# switch_7btn.net
KiCad netlist of a schematic drawn in EAGLE
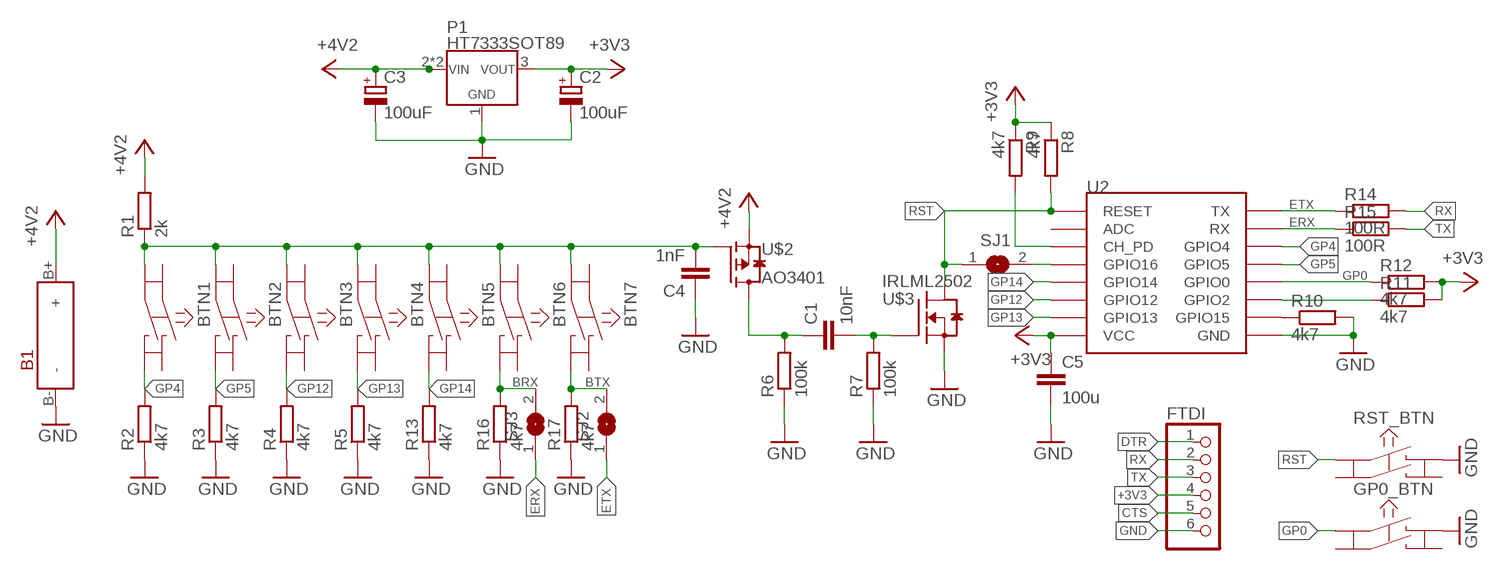
[diagram p0: schematic, sheet 1]

(export (version "E")
  (design (tool "Eeschema 10.0.6"))
  (components
    (comp (ref "B1")
      (value "18650_1X")
      (footprint "eagle-import:18650_HOLDER_1X")
      (libsource (lib "eagle-import") (part "18650_1X"))
    )
    (comp (ref "BTN1")
      (value "KSM611A")
      (footprint "eagle-import:KSM611A")
      (libsource (lib "eagle-import") (part "KSM611A"))
    )
    (comp (ref "BTN2")
      (value "KSM611A")
      (footprint "eagle-import:KSM611A")
      (libsource (lib "eagle-import") (part "KSM611A"))
    )
    (comp (ref "BTN3")
      (value "KSM611A")
      (footprint "eagle-import:KSM611A")
      (libsource (lib "eagle-import") (part "KSM611A"))
    )
    (comp (ref "BTN4")
      (value "KSM611A")
      (footprint "eagle-import:KSM611A")
      (libsource (lib "eagle-import") (part "KSM611A"))
    )
    (comp (ref "BTN5")
      (value "KSM611A")
      (footprint "eagle-import:KSM611A")
      (libsource (lib "eagle-import") (part "KSM611A"))
    )
    (comp (ref "BTN6")
      (value "KSM611A")
      (footprint "eagle-import:KSM611A")
      (libsource (lib "eagle-import") (part "KSM611A"))
    )
    (comp (ref "BTN7")
      (value "KSM611A")
      (footprint "eagle-import:KSM611A")
      (libsource (lib "eagle-import") (part "KSM611A"))
    )
    (comp (ref "C1")
      (value "10nF")
      (footprint "eagle-import:C025-025X050")
      (libsource (lib "eagle-import") (part "C-EU025-025X050"))
    )
    (comp (ref "C2")
      (value "100uF")
      (footprint "eagle-import:E5-8,5")
      (libsource (lib "eagle-import") (part "CPOL-EUE5-8.5"))
    )
    (comp (ref "C3")
      (value "100uF")
      (footprint "eagle-import:E5-8,5")
      (libsource (lib "eagle-import") (part "CPOL-EUE5-8.5"))
    )
    (comp (ref "C4")
      (value "1nF")
      (footprint "eagle-import:C025-025X050")
      (libsource (lib "eagle-import") (part "C-EU025-025X050"))
    )
    (comp (ref "C5")
      (value "100u")
      (footprint "eagle-import:C1206")
      (libsource (lib "eagle-import") (part "C-EUC1206"))
    )
    (comp (ref "FTDI")
      (value "PINHD-1X06_2.54-S")
      (footprint "eagle-import:1X06-S")
      (libsource (lib "eagle-import") (part "PINHD-1X06_2.54-S"))
    )
    (comp (ref "GP0_BTN")
      (value "KSM611A")
      (footprint "eagle-import:KSM611A")
      (libsource (lib "eagle-import") (part "KSM611A"))
    )
    (comp (ref "P1")
      (value "HT7333SOT89")
      (footprint "eagle-import:SOT89")
      (libsource (lib "eagle-import") (part "HT7333SOT89"))
    )
    (comp (ref "R1")
      (value "2k")
      (footprint "eagle-import:MULTI_RESISTOR")
      (libsource (lib "eagle-import") (part "R-EU_MULTI"))
    )
    (comp (ref "R2")
      (value "4k7")
      (footprint "eagle-import:MULTI_RESISTOR")
      (libsource (lib "eagle-import") (part "R-EU_MULTI"))
    )
    (comp (ref "R3")
      (value "4k7")
      (footprint "eagle-import:MULTI_RESISTOR")
      (libsource (lib "eagle-import") (part "R-EU_MULTI"))
    )
    (comp (ref "R4")
      (value "4k7")
      (footprint "eagle-import:MULTI_RESISTOR")
      (libsource (lib "eagle-import") (part "R-EU_MULTI"))
    )
    (comp (ref "R5")
      (value "4k7")
      (footprint "eagle-import:MULTI_RESISTOR")
      (libsource (lib "eagle-import") (part "R-EU_MULTI"))
    )
    (comp (ref "R6")
      (value "100k")
      (footprint "eagle-import:MULTI_RESISTOR")
      (libsource (lib "eagle-import") (part "R-EU_MULTI"))
    )
    (comp (ref "R7")
      (value "100k")
      (footprint "eagle-import:MULTI_RESISTOR")
      (libsource (lib "eagle-import") (part "R-EU_MULTI"))
    )
    (comp (ref "R8")
      (value "4k7")
      (footprint "eagle-import:MULTI_RESISTOR")
      (libsource (lib "eagle-import") (part "R-EU_MULTI"))
    )
    (comp (ref "R9")
      (value "4k7")
      (footprint "eagle-import:MULTI_RESISTOR")
      (libsource (lib "eagle-import") (part "R-EU_MULTI"))
    )
    (comp (ref "R10")
      (value "4k7")
      (footprint "eagle-import:MULTI_RESISTOR")
      (libsource (lib "eagle-import") (part "R-EU_MULTI"))
    )
    (comp (ref "R11")
      (value "4k7")
      (footprint "eagle-import:MULTI_RESISTOR")
      (libsource (lib "eagle-import") (part "R-EU_MULTI"))
    )
    (comp (ref "R12")
      (value "4k7")
      (footprint "eagle-import:MULTI_RESISTOR")
      (libsource (lib "eagle-import") (part "R-EU_MULTI"))
    )
    (comp (ref "R13")
      (value "4k7")
      (footprint "eagle-import:MULTI_RESISTOR")
      (libsource (lib "eagle-import") (part "R-EU_MULTI"))
    )
    (comp (ref "R14")
      (value "100R")
      (footprint "eagle-import:MULTI_RESISTOR")
      (libsource (lib "eagle-import") (part "R-EU_MULTI"))
    )
    (comp (ref "R15")
      (value "100R")
      (footprint "eagle-import:MULTI_RESISTOR")
      (libsource (lib "eagle-import") (part "R-EU_MULTI"))
    )
    (comp (ref "R16")
      (value "4k7")
      (footprint "eagle-import:MULTI_RESISTOR")
      (libsource (lib "eagle-import") (part "R-EU_MULTI"))
    )
    (comp (ref "R17")
      (value "4k7")
      (footprint "eagle-import:MULTI_RESISTOR")
      (libsource (lib "eagle-import") (part "R-EU_MULTI"))
    )
    (comp (ref "RST_BTN")
      (value "KSM611A")
      (footprint "eagle-import:KSM611A")
      (libsource (lib "eagle-import") (part "KSM611A"))
    )
    (comp (ref "SJ1") (value "SJ") (footprint "eagle-import:SJ") (libsource (lib "eagle-import") (part "SJ")))
    (comp (ref "SJ2") (value "SJ") (footprint "eagle-import:SJ") (libsource (lib "eagle-import") (part "SJ")))
    (comp (ref "SJ3") (value "SJ") (footprint "eagle-import:SJ") (libsource (lib "eagle-import") (part "SJ")))
    (comp (ref "U$2")
      (value "AO3401")
      (footprint "eagle-import:SOT23")
      (libsource (lib "eagle-import") (part "P-CH_AO3401"))
    )
    (comp (ref "U$3")
      (value "IRLML2502")
      (footprint "eagle-import:SOT23")
      (libsource (lib "eagle-import") (part "N-CH_IRLML2502"))
    )
    (comp (ref "U2")
      (value "ESP12SMD")
      (footprint "eagle-import:ESP12-SMD")
      (libsource (lib "eagle-import") (part "ESP12SMD"))
    )
  )
  (nets
    (net (code "1") (name "+3V3") (class "Default")
      (node (ref "C2") (pin "+") (pinfunction "+_+") (pintype "passive"))
      (node (ref "C5") (pin "1") (pinfunction "1_1") (pintype "passive"))
      (node (ref "FTDI") (pin "4") (pinfunction "4_4") (pintype "passive"))
      (node (ref "P1") (pin "3") (pinfunction "VOUT_3") (pintype "power_in"))
      (node (ref "R11") (pin "2@1") (pinfunction "2_2@1") (pintype "passive"))
      (node (ref "R11") (pin "2@2") (pinfunction "2_2@2") (pintype "passive"))
      (node (ref "R12") (pin "2@1") (pinfunction "2_2@1") (pintype "passive"))
      (node (ref "R12") (pin "2@2") (pinfunction "2_2@2") (pintype "passive"))
      (node (ref "R8") (pin "1@1") (pinfunction "1_1@1") (pintype "passive"))
      (node (ref "R8") (pin "1@2") (pinfunction "1_1@2") (pintype "passive"))
      (node (ref "R9") (pin "1@1") (pinfunction "1_1@1") (pintype "passive"))
      (node (ref "R9") (pin "1@2") (pinfunction "1_1@2") (pintype "passive"))
      (node (ref "U2") (pin "VCC") (pinfunction "VCC_VCC") (pintype "bidirectional"))
    )
    (net (code "2") (name "+4V2") (class "Default")
      (node (ref "B1") (pin "B+") (pinfunction "+_B+") (pintype "power_in"))
      (node (ref "C3") (pin "+") (pinfunction "+_+") (pintype "passive"))
      (node (ref "P1") (pin "2") (pinfunction "VIN_2") (pintype "power_in"))
      (node (ref "P1") (pin "2@1") (pinfunction "VIN_2@1") (pintype "power_in"))
      (node (ref "R1") (pin "2@1") (pinfunction "2_2@1") (pintype "passive"))
      (node (ref "R1") (pin "2@2") (pinfunction "2_2@2") (pintype "passive"))
      (node (ref "U$2") (pin "2") (pinfunction "S_2") (pintype "passive"))
    )
    (net (code "3") (name "/BRX") (class "Default")
      (node (ref "BTN6") (pin "D") (pinfunction "D_D") (pintype "passive"))
      (node (ref "R16") (pin "2@1") (pinfunction "2_2@1") (pintype "passive"))
      (node (ref "R16") (pin "2@2") (pinfunction "2_2@2") (pintype "passive"))
      (node (ref "SJ3") (pin "2") (pinfunction "2_2") (pintype "passive"))
    )
    (net (code "4") (name "/BTX") (class "Default")
      (node (ref "BTN7") (pin "D") (pinfunction "D_D") (pintype "passive"))
      (node (ref "R17") (pin "2@1") (pinfunction "2_2@1") (pintype "passive"))
      (node (ref "R17") (pin "2@2") (pinfunction "2_2@2") (pintype "passive"))
      (node (ref "SJ2") (pin "2") (pinfunction "2_2") (pintype "passive"))
    )
    (net (code "5") (name "CTS") (class "Default")
      (node (ref "FTDI") (pin "5") (pinfunction "5_5") (pintype "passive"))
    )
    (net (code "6") (name "DTR") (class "Default")
      (node (ref "FTDI") (pin "1") (pinfunction "1_1") (pintype "passive"))
    )
    (net (code "7") (name "ERX") (class "Default")
      (node (ref "R15") (pin "1@1") (pinfunction "1_1@1") (pintype "passive"))
      (node (ref "R15") (pin "1@2") (pinfunction "1_1@2") (pintype "passive"))
      (node (ref "SJ3") (pin "1") (pinfunction "1_1") (pintype "passive"))
      (node (ref "U2") (pin "RXD0") (pinfunction "RX_RXD0") (pintype "bidirectional"))
    )
    (net (code "8") (name "ETX") (class "Default")
      (node (ref "R14") (pin "1@1") (pinfunction "1_1@1") (pintype "passive"))
      (node (ref "R14") (pin "1@2") (pinfunction "1_1@2") (pintype "passive"))
      (node (ref "SJ2") (pin "1") (pinfunction "1_1") (pintype "passive"))
      (node (ref "U2") (pin "TXD0") (pinfunction "TX_TXD0") (pintype "bidirectional"))
    )
    (net (code "9") (name "GND") (class "Default")
      (node (ref "B1") (pin "B-") (pinfunction "-_B-") (pintype "power_in"))
      (node (ref "C2") (pin "-") (pinfunction "-_-") (pintype "passive"))
      (node (ref "C3") (pin "-") (pinfunction "-_-") (pintype "passive"))
      (node (ref "C4") (pin "1") (pinfunction "1_1") (pintype "passive"))
      (node (ref "C5") (pin "2") (pinfunction "2_2") (pintype "passive"))
      (node (ref "FTDI") (pin "6") (pinfunction "6_6") (pintype "passive"))
      (node (ref "GP0_BTN") (pin "B") (pinfunction "B_B") (pintype "passive"))
      (node (ref "P1") (pin "1") (pinfunction "GND_1") (pintype "power_in"))
      (node (ref "R10") (pin "2@1") (pinfunction "2_2@1") (pintype "passive"))
      (node (ref "R10") (pin "2@2") (pinfunction "2_2@2") (pintype "passive"))
      (node (ref "R13") (pin "1@1") (pinfunction "1_1@1") (pintype "passive"))
      (node (ref "R13") (pin "1@2") (pinfunction "1_1@2") (pintype "passive"))
      (node (ref "R16") (pin "1@1") (pinfunction "1_1@1") (pintype "passive"))
      (node (ref "R16") (pin "1@2") (pinfunction "1_1@2") (pintype "passive"))
      (node (ref "R17") (pin "1@1") (pinfunction "1_1@1") (pintype "passive"))
      (node (ref "R17") (pin "1@2") (pinfunction "1_1@2") (pintype "passive"))
      (node (ref "R2") (pin "1@1") (pinfunction "1_1@1") (pintype "passive"))
      (node (ref "R2") (pin "1@2") (pinfunction "1_1@2") (pintype "passive"))
      (node (ref "R3") (pin "1@1") (pinfunction "1_1@1") (pintype "passive"))
      (node (ref "R3") (pin "1@2") (pinfunction "1_1@2") (pintype "passive"))
      (node (ref "R4") (pin "1@1") (pinfunction "1_1@1") (pintype "passive"))
      (node (ref "R4") (pin "1@2") (pinfunction "1_1@2") (pintype "passive"))
      (node (ref "R5") (pin "1@1") (pinfunction "1_1@1") (pintype "passive"))
      (node (ref "R5") (pin "1@2") (pinfunction "1_1@2") (pintype "passive"))
      (node (ref "R6") (pin "1@1") (pinfunction "1_1@1") (pintype "passive"))
      (node (ref "R6") (pin "1@2") (pinfunction "1_1@2") (pintype "passive"))
      (node (ref "R7") (pin "1@1") (pinfunction "1_1@1") (pintype "passive"))
      (node (ref "R7") (pin "1@2") (pinfunction "1_1@2") (pintype "passive"))
      (node (ref "RST_BTN") (pin "B") (pinfunction "B_B") (pintype "passive"))
      (node (ref "U$3") (pin "2") (pinfunction "S_2") (pintype "passive"))
      (node (ref "U2") (pin "GND") (pinfunction "GND_GND") (pintype "bidirectional"))
    )
    (net (code "10") (name "GP0") (class "Default")
      (node (ref "GP0_BTN") (pin "A") (pinfunction "A_A") (pintype "passive"))
      (node (ref "R12") (pin "1@1") (pinfunction "1_1@1") (pintype "passive"))
      (node (ref "R12") (pin "1@2") (pinfunction "1_1@2") (pintype "passive"))
      (node (ref "U2") (pin "GPIO0") (pinfunction "GPIO0_GPIO0") (pintype "bidirectional"))
    )
    (net (code "11") (name "GP4") (class "Default")
      (node (ref "BTN1") (pin "D") (pinfunction "D_D") (pintype "passive"))
      (node (ref "R2") (pin "2@1") (pinfunction "2_2@1") (pintype "passive"))
      (node (ref "R2") (pin "2@2") (pinfunction "2_2@2") (pintype "passive"))
      (node (ref "U2") (pin "GPIO4") (pinfunction "GPIO4_GPIO4") (pintype "bidirectional"))
    )
    (net (code "12") (name "GP5") (class "Default")
      (node (ref "BTN2") (pin "D") (pinfunction "D_D") (pintype "passive"))
      (node (ref "R3") (pin "2@1") (pinfunction "2_2@1") (pintype "passive"))
      (node (ref "R3") (pin "2@2") (pinfunction "2_2@2") (pintype "passive"))
      (node (ref "U2") (pin "GPIO5") (pinfunction "GPIO5_GPIO5") (pintype "bidirectional"))
    )
    (net (code "13") (name "GP12") (class "Default")
      (node (ref "BTN3") (pin "D") (pinfunction "D_D") (pintype "passive"))
      (node (ref "R4") (pin "2@1") (pinfunction "2_2@1") (pintype "passive"))
      (node (ref "R4") (pin "2@2") (pinfunction "2_2@2") (pintype "passive"))
      (node (ref "U2") (pin "GPIO12") (pinfunction "GPIO12_GPIO12") (pintype "bidirectional"))
    )
    (net (code "14") (name "GP13") (class "Default")
      (node (ref "BTN4") (pin "D") (pinfunction "D_D") (pintype "passive"))
      (node (ref "R5") (pin "2@1") (pinfunction "2_2@1") (pintype "passive"))
      (node (ref "R5") (pin "2@2") (pinfunction "2_2@2") (pintype "passive"))
      (node (ref "U2") (pin "GPIO13") (pinfunction "GPIO13_GPIO13") (pintype "bidirectional"))
    )
    (net (code "15") (name "GP14") (class "Default")
      (node (ref "BTN5") (pin "D") (pinfunction "D_D") (pintype "passive"))
      (node (ref "R13") (pin "2@1") (pinfunction "2_2@1") (pintype "passive"))
      (node (ref "R13") (pin "2@2") (pinfunction "2_2@2") (pintype "passive"))
      (node (ref "U2") (pin "GPIO14") (pinfunction "GPIO14_GPIO14") (pintype "bidirectional"))
    )
    (net (code "16") (name "Net-(R9-2-Pad2@1)") (class "Default")
      (node (ref "R9") (pin "2@1") (pinfunction "2_2@1") (pintype "passive"))
      (node (ref "R9") (pin "2@2") (pinfunction "2_2@2") (pintype "passive"))
      (node (ref "U2") (pin "CH_PD") (pinfunction "CH_PD_CH_PD") (pintype "bidirectional"))
    )
    (net (code "17") (name "Net-(R10-1-Pad1@1)") (class "Default")
      (node (ref "R10") (pin "1@1") (pinfunction "1_1@1") (pintype "passive"))
      (node (ref "R10") (pin "1@2") (pinfunction "1_1@2") (pintype "passive"))
      (node (ref "U2") (pin "GPIO15") (pinfunction "GPIO15_GPIO15") (pintype "bidirectional"))
    )
    (net (code "18") (name "Net-(R11-1-Pad1@1)") (class "Default")
      (node (ref "R11") (pin "1@1") (pinfunction "1_1@1") (pintype "passive"))
      (node (ref "R11") (pin "1@2") (pinfunction "1_1@2") (pintype "passive"))
      (node (ref "U2") (pin "GPIO2") (pinfunction "GPIO2_GPIO2") (pintype "bidirectional"))
    )
    (net (code "19") (name "Net-(SJ1-Pad2)") (class "Default")
      (node (ref "SJ1") (pin "2") (pinfunction "2_2") (pintype "passive"))
      (node (ref "U2") (pin "GPIO16") (pinfunction "GPIO16_GPIO16") (pintype "bidirectional"))
    )
    (net (code "20") (name "Net-(U$2-D)") (class "Default")
      (node (ref "C1") (pin "1") (pinfunction "1_1") (pintype "passive"))
      (node (ref "R6") (pin "2@1") (pinfunction "2_2@1") (pintype "passive"))
      (node (ref "R6") (pin "2@2") (pinfunction "2_2@2") (pintype "passive"))
      (node (ref "U$2") (pin "3") (pinfunction "D_3") (pintype "passive"))
    )
    (net (code "21") (name "Net-(U$2-G)") (class "Default")
      (node (ref "BTN1") (pin "C") (pinfunction "C_C") (pintype "passive"))
      (node (ref "BTN2") (pin "C") (pinfunction "C_C") (pintype "passive"))
      (node (ref "BTN3") (pin "C") (pinfunction "C_C") (pintype "passive"))
      (node (ref "BTN4") (pin "C") (pinfunction "C_C") (pintype "passive"))
      (node (ref "BTN5") (pin "C") (pinfunction "C_C") (pintype "passive"))
      (node (ref "BTN6") (pin "C") (pinfunction "C_C") (pintype "passive"))
      (node (ref "BTN7") (pin "C") (pinfunction "C_C") (pintype "passive"))
      (node (ref "C4") (pin "2") (pinfunction "2_2") (pintype "passive"))
      (node (ref "R1") (pin "1@1") (pinfunction "1_1@1") (pintype "passive"))
      (node (ref "R1") (pin "1@2") (pinfunction "1_1@2") (pintype "passive"))
      (node (ref "U$2") (pin "1") (pinfunction "G_1") (pintype "passive"))
    )
    (net (code "22") (name "Net-(U$3-G)") (class "Default")
      (node (ref "C1") (pin "2") (pinfunction "2_2") (pintype "passive"))
      (node (ref "R7") (pin "2@1") (pinfunction "2_2@1") (pintype "passive"))
      (node (ref "R7") (pin "2@2") (pinfunction "2_2@2") (pintype "passive"))
      (node (ref "U$3") (pin "1") (pinfunction "G_1") (pintype "passive"))
    )
    (net (code "23") (name "RST") (class "Default")
      (node (ref "R8") (pin "2@1") (pinfunction "2_2@1") (pintype "passive"))
      (node (ref "R8") (pin "2@2") (pinfunction "2_2@2") (pintype "passive"))
      (node (ref "RST_BTN") (pin "A") (pinfunction "A_A") (pintype "passive"))
      (node (ref "SJ1") (pin "1") (pinfunction "1_1") (pintype "passive"))
      (node (ref "U$3") (pin "3") (pinfunction "D_3") (pintype "passive"))
      (node (ref "U2") (pin "RESET") (pinfunction "RESET_RESET") (pintype "bidirectional"))
    )
    (net (code "24") (name "RX") (class "Default")
      (node (ref "FTDI") (pin "2") (pinfunction "2_2") (pintype "passive"))
      (node (ref "R14") (pin "2@1") (pinfunction "2_2@1") (pintype "passive"))
      (node (ref "R14") (pin "2@2") (pinfunction "2_2@2") (pintype "passive"))
    )
    (net (code "25") (name "TX") (class "Default")
      (node (ref "FTDI") (pin "3") (pinfunction "3_3") (pintype "passive"))
      (node (ref "R15") (pin "2@1") (pinfunction "2_2@1") (pintype "passive"))
      (node (ref "R15") (pin "2@2") (pinfunction "2_2@2") (pintype "passive"))
    )
    (net (code "26") (name "unconnected-(BTN1-PadA)") (class "Default")
      (node (ref "BTN1") (pin "A") (pinfunction "A_A") (pintype "passive"))
    )
    (net (code "27") (name "unconnected-(BTN1-PadB)") (class "Default")
      (node (ref "BTN1") (pin "B") (pinfunction "B_B") (pintype "passive"))
    )
    (net (code "28") (name "unconnected-(BTN2-PadA)") (class "Default")
      (node (ref "BTN2") (pin "A") (pinfunction "A_A") (pintype "passive"))
    )
    (net (code "29") (name "unconnected-(BTN2-PadB)") (class "Default")
      (node (ref "BTN2") (pin "B") (pinfunction "B_B") (pintype "passive"))
    )
    (net (code "30") (name "unconnected-(BTN3-PadA)") (class "Default")
      (node (ref "BTN3") (pin "A") (pinfunction "A_A") (pintype "passive"))
    )
    (net (code "31") (name "unconnected-(BTN3-PadB)") (class "Default")
      (node (ref "BTN3") (pin "B") (pinfunction "B_B") (pintype "passive"))
    )
    (net (code "32") (name "unconnected-(BTN4-PadA)") (class "Default")
      (node (ref "BTN4") (pin "A") (pinfunction "A_A") (pintype "passive"))
    )
    (net (code "33") (name "unconnected-(BTN4-PadB)") (class "Default")
      (node (ref "BTN4") (pin "B") (pinfunction "B_B") (pintype "passive"))
    )
    (net (code "34") (name "unconnected-(BTN5-PadA)") (class "Default")
      (node (ref "BTN5") (pin "A") (pinfunction "A_A") (pintype "passive"))
    )
    (net (code "35") (name "unconnected-(BTN5-PadB)") (class "Default")
      (node (ref "BTN5") (pin "B") (pinfunction "B_B") (pintype "passive"))
    )
    (net (code "36") (name "unconnected-(BTN6-PadA)") (class "Default")
      (node (ref "BTN6") (pin "A") (pinfunction "A_A") (pintype "passive"))
    )
    (net (code "37") (name "unconnected-(BTN6-PadB)") (class "Default")
      (node (ref "BTN6") (pin "B") (pinfunction "B_B") (pintype "passive"))
    )
    (net (code "38") (name "unconnected-(BTN7-PadA)") (class "Default")
      (node (ref "BTN7") (pin "A") (pinfunction "A_A") (pintype "passive"))
    )
    (net (code "39") (name "unconnected-(BTN7-PadB)") (class "Default")
      (node (ref "BTN7") (pin "B") (pinfunction "B_B") (pintype "passive"))
    )
    (net (code "40") (name "unconnected-(GP0_BTN-PadC)") (class "Default")
      (node (ref "GP0_BTN") (pin "C") (pinfunction "C_C") (pintype "passive"))
    )
    (net (code "41") (name "unconnected-(GP0_BTN-PadD)") (class "Default")
      (node (ref "GP0_BTN") (pin "D") (pinfunction "D_D") (pintype "passive"))
    )
    (net (code "42") (name "unconnected-(RST_BTN-PadC)") (class "Default")
      (node (ref "RST_BTN") (pin "C") (pinfunction "C_C") (pintype "passive"))
    )
    (net (code "43") (name "unconnected-(RST_BTN-PadD)") (class "Default")
      (node (ref "RST_BTN") (pin "D") (pinfunction "D_D") (pintype "passive"))
    )
    (net (code "44") (name "unconnected-(U2-PadADC)") (class "Default")
      (node (ref "U2") (pin "ADC") (pinfunction "ADC_ADC") (pintype "bidirectional"))
    )
  )
)
